# tps63020-buck-boost-flashlight-driver-te.net
KiCad netlist of a schematic drawn in EAGLE
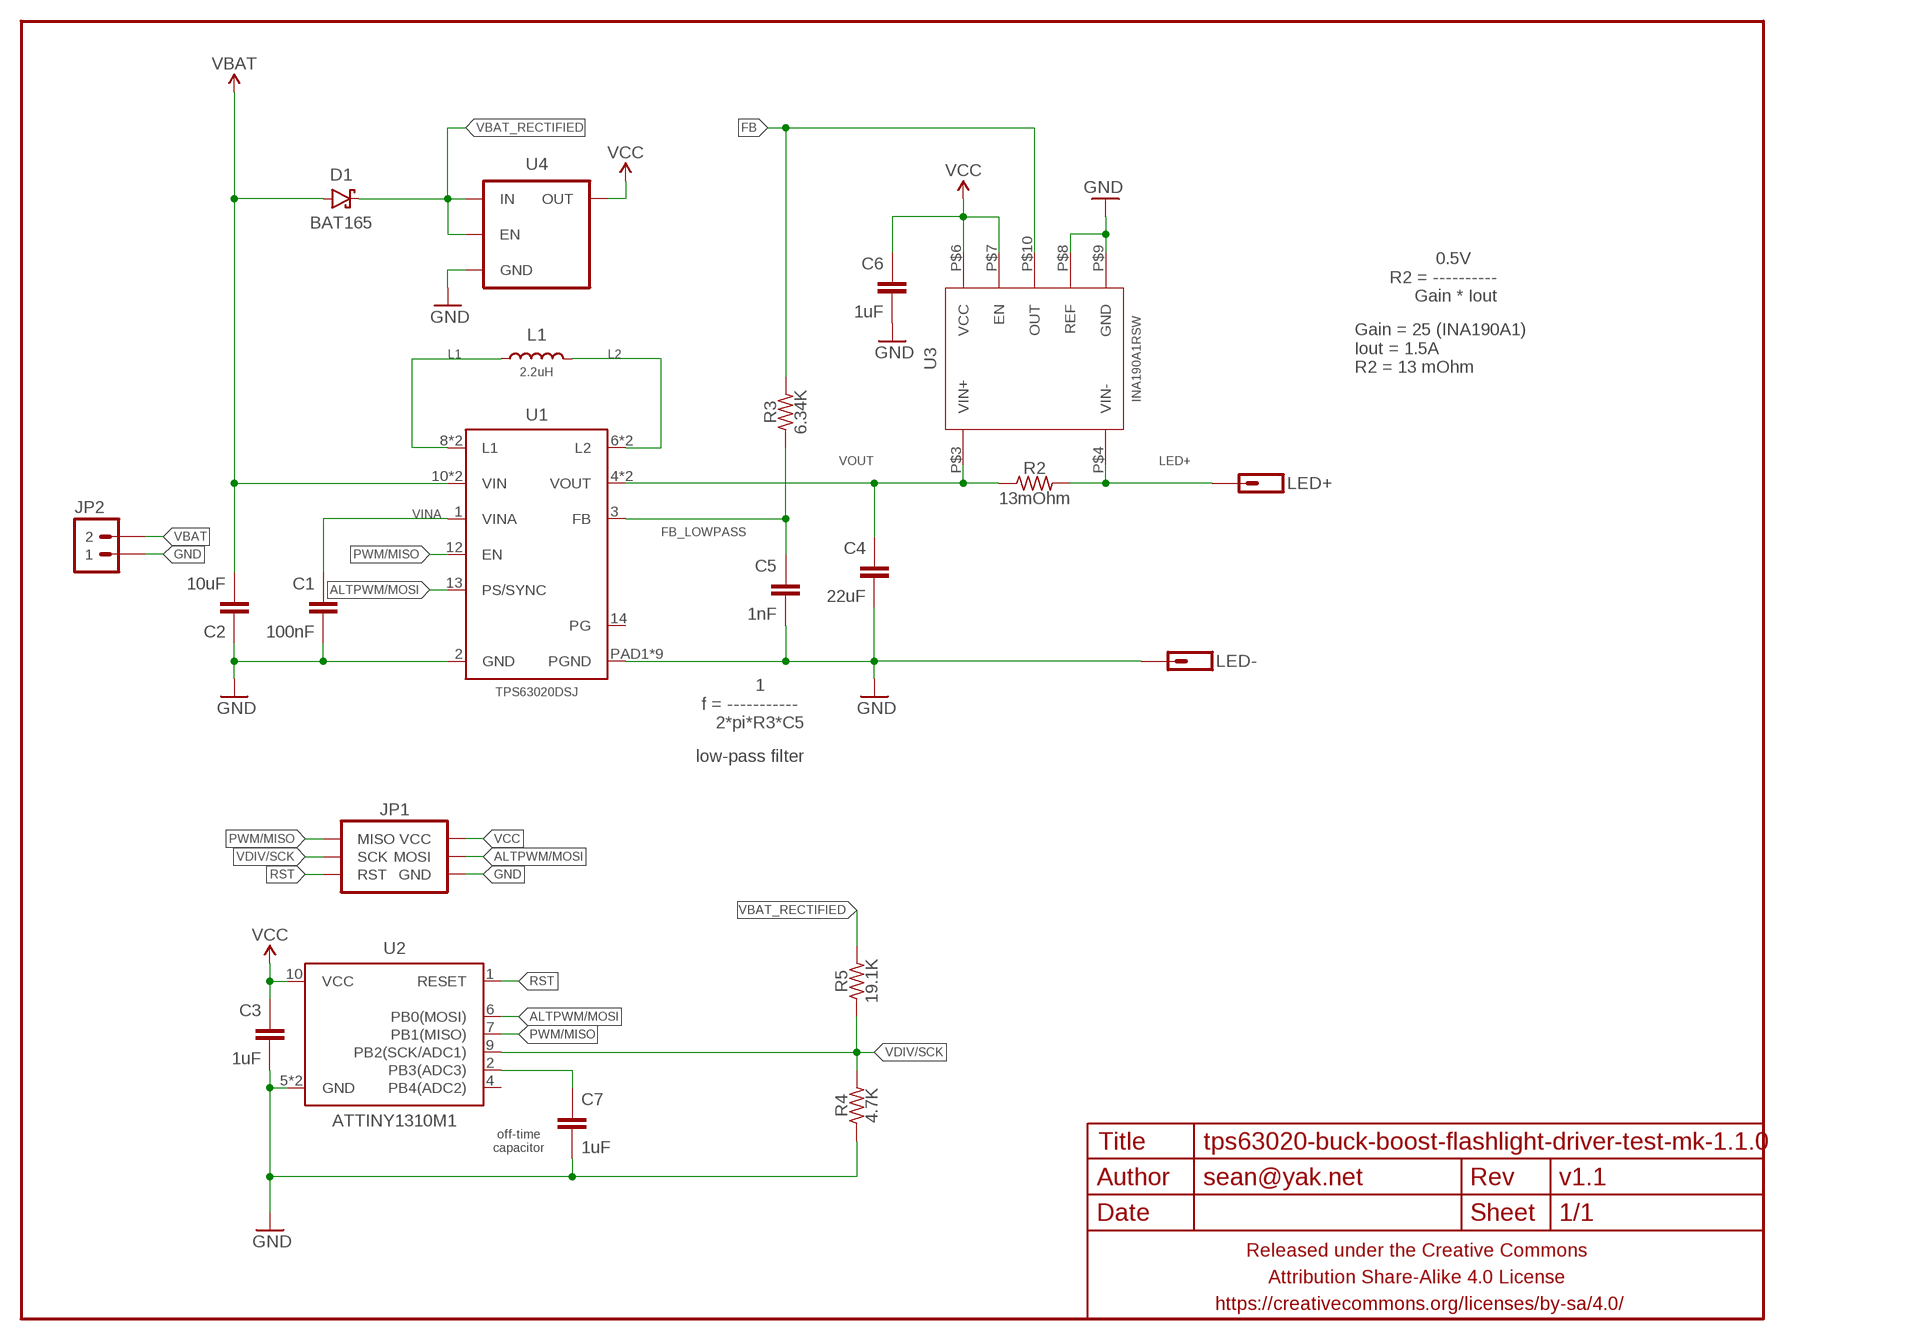
[diagram p0: schematic, sheet 1]

(export (version "E")
  (design (tool "Eeschema 10.0.6"))
  (components
    (comp (ref "C1")
      (value "100nF")
      (footprint "eagle-import:C0402")
      (libsource (lib "eagle-import") (part "CAPACITOR-CERAMICC0402"))
    )
    (comp (ref "C2")
      (value "10uF")
      (footprint "eagle-import:C0805-TIGHTER")
      (libsource (lib "eagle-import") (part "CAPACITOR-CERAMICC0805-TIGHTER"))
    )
    (comp (ref "C3")
      (value "1uF")
      (footprint "eagle-import:C0402")
      (libsource (lib "eagle-import") (part "CAPACITOR-CERAMICC0402"))
    )
    (comp (ref "C4")
      (value "22uF")
      (footprint "eagle-import:C1206")
      (libsource (lib "eagle-import") (part "CAPACITOR-CERAMICC1206"))
    )
    (comp (ref "C5")
      (value "1nF")
      (footprint "eagle-import:C0402")
      (libsource (lib "eagle-import") (part "CAPACITOR-CERAMICC0402"))
    )
    (comp (ref "C6")
      (value "1uF")
      (footprint "eagle-import:C0402")
      (libsource (lib "eagle-import") (part "CAPACITOR-CERAMICC0402"))
    )
    (comp (ref "C7")
      (value "1uF")
      (footprint "eagle-import:C0402")
      (libsource (lib "eagle-import") (part "CAPACITOR-CERAMICC0402"))
    )
    (comp (ref "D1")
      (value "BAT165")
      (footprint "eagle-import:SOD323-SCHOTTKY")
      (libsource (lib "eagle-import") (part "DIODE-SCHOTTKYSOD323"))
    )
    (comp (ref "FRAME1")
      (value "FRAME-LETTERNO_PACKAGE")
      (footprint "eagle-import:DUMMY")
      (fields
        (field (name "DESIGNER") "Nobody")
        (field (name "VERSION") "v01")
        (field (name "DESIGNER_1") "sean@yak.net")
        (field (name "VERSION_1") "v1.1")
      )
      (libsource (lib "eagle-import") (part "FRAME-LETTERNO_PACKAGE"))
    )
    (comp (ref "JP1")
      (value "AVR_SPI_PRG_6PTH-1.27MM")
      (footprint "eagle-import:2X3-1.27MM-PTH")
      (libsource (lib "eagle-import") (part "AVR_SPI_PRG_6PTH-1.27MM"))
    )
    (comp (ref "JP2")
      (value "M02PTH-2MM")
      (footprint "eagle-import:1X02-2MM-PTH")
      (libsource (lib "eagle-import") (part "M02PTH-2MM"))
    )
    (comp (ref "L1")
      (value "2.2uH")
      (footprint "eagle-import:XAL50X0")
      (libsource (lib "eagle-import") (part "INDUCTORXAL50X0"))
    )
    (comp (ref "LED+")
      (value "M01PTH-1MM-CIR-NS")
      (footprint "eagle-import:1X01-1MM-CIR-NS")
      (libsource (lib "eagle-import") (part "M01PTH-1MM-CIR-NS"))
    )
    (comp (ref "LED-")
      (value "M01PTH-1MM-CIR-NS")
      (footprint "eagle-import:1X01-1MM-CIR-NS")
      (libsource (lib "eagle-import") (part "M01PTH-1MM-CIR-NS"))
    )
    (comp (ref "R2")
      (value "13mOhm")
      (footprint "eagle-import:R1206")
      (libsource (lib "eagle-import") (part "RESISTORR1206"))
    )
    (comp (ref "R3")
      (value "6.34K")
      (footprint "eagle-import:R0402")
      (libsource (lib "eagle-import") (part "RESISTORR0402"))
    )
    (comp (ref "R4")
      (value "4.7K")
      (footprint "eagle-import:R0402")
      (libsource (lib "eagle-import") (part "RESISTORR0402"))
    )
    (comp (ref "R5")
      (value "19.1K")
      (footprint "eagle-import:R0402")
      (libsource (lib "eagle-import") (part "RESISTORR0402"))
    )
    (comp (ref "U1")
      (value "TPS63020DSJ")
      (footprint "eagle-import:VSON-14-4MMX3MM")
      (libsource (lib "eagle-import") (part "TPS63020DSJ"))
    )
    (comp (ref "U2")
      (value "ATTINY1310M1")
      (footprint "eagle-import:QFN10(2X5)")
      (libsource (lib "eagle-import") (part "ATTINY1310M1"))
    )
    (comp (ref "U3")
      (value "INA190A1RSW")
      (footprint "eagle-import:UQFN-10")
      (libsource (lib "eagle-import") (part "INA190RSW"))
    )
    (comp (ref "U4")
      (value "V_REG_ENTLV700")
      (footprint "eagle-import:SC70")
      (libsource (lib "eagle-import") (part "V_REG_ENTLV700"))
    )
  )
  (nets
    (net (code "1") (name "/FB_LOWPASS") (class "Default")
      (node (ref "C5") (pin "1") (pinfunction "1_1") (pintype "passive"))
      (node (ref "R3") (pin "1") (pinfunction "1_1") (pintype "passive"))
      (node (ref "U1") (pin "3") (pinfunction "FB_3") (pintype "bidirectional"))
    )
    (net (code "2") (name "/L1") (class "Default")
      (node (ref "L1") (pin "P$1") (pinfunction "1_P$1") (pintype "passive"))
      (node (ref "U1") (pin "8") (pinfunction "L1_8") (pintype "bidirectional"))
      (node (ref "U1") (pin "9") (pinfunction "L1_9") (pintype "bidirectional"))
    )
    (net (code "3") (name "/L2") (class "Default")
      (node (ref "L1") (pin "P$2") (pinfunction "2_P$2") (pintype "passive"))
      (node (ref "U1") (pin "6") (pinfunction "L2_6") (pintype "bidirectional"))
      (node (ref "U1") (pin "7") (pinfunction "L2_7") (pintype "bidirectional"))
    )
    (net (code "4") (name "/LED+") (class "Default")
      (node (ref "LED+") (pin "1") (pinfunction "1_1") (pintype "passive"))
      (node (ref "R2") (pin "2") (pinfunction "2_2") (pintype "passive"))
      (node (ref "U3") (pin "P$4") (pinfunction "VIN-_P$4") (pintype "bidirectional"))
    )
    (net (code "5") (name "/VINA") (class "Default")
      (node (ref "C1") (pin "1") (pinfunction "1_1") (pintype "passive"))
      (node (ref "U1") (pin "1") (pinfunction "VINA_1") (pintype "bidirectional"))
    )
    (net (code "6") (name "/VOUT") (class "Default")
      (node (ref "C4") (pin "1") (pinfunction "1_1") (pintype "passive"))
      (node (ref "R2") (pin "1") (pinfunction "1_1") (pintype "passive"))
      (node (ref "U1") (pin "4") (pinfunction "VOUT_4") (pintype "bidirectional"))
      (node (ref "U1") (pin "5") (pinfunction "VOUT_5") (pintype "bidirectional"))
      (node (ref "U3") (pin "P$3") (pinfunction "VIN+_P$3") (pintype "bidirectional"))
    )
    (net (code "7") (name "ALTPWM{slash}MOSI") (class "Default")
      (node (ref "JP1") (pin "4") (pinfunction "MOSI_4") (pintype "passive"))
      (node (ref "U1") (pin "13") (pinfunction "PS/SYNC_13") (pintype "bidirectional"))
      (node (ref "U2") (pin "6") (pinfunction "PB0(MOSI)_6") (pintype "bidirectional"))
    )
    (net (code "8") (name "FB") (class "Default")
      (node (ref "R3") (pin "2") (pinfunction "2_2") (pintype "passive"))
      (node (ref "U3") (pin "P$10") (pinfunction "OUT_P$10") (pintype "bidirectional"))
    )
    (net (code "9") (name "GND") (class "Default")
      (node (ref "C1") (pin "2") (pinfunction "2_2") (pintype "passive"))
      (node (ref "C2") (pin "1") (pinfunction "1_1") (pintype "passive"))
      (node (ref "C3") (pin "2") (pinfunction "2_2") (pintype "passive"))
      (node (ref "C4") (pin "2") (pinfunction "2_2") (pintype "passive"))
      (node (ref "C5") (pin "2") (pinfunction "2_2") (pintype "passive"))
      (node (ref "C6") (pin "2") (pinfunction "2_2") (pintype "passive"))
      (node (ref "C7") (pin "2") (pinfunction "2_2") (pintype "passive"))
      (node (ref "JP1") (pin "6") (pinfunction "GND_6") (pintype "passive"))
      (node (ref "JP2") (pin "P$1") (pinfunction "1_P$1") (pintype "passive"))
      (node (ref "LED-") (pin "1") (pinfunction "1_1") (pintype "passive"))
      (node (ref "R4") (pin "1") (pinfunction "1_1") (pintype "passive"))
      (node (ref "U1") (pin "2") (pinfunction "GND_2") (pintype "bidirectional"))
      (node (ref "U1") (pin "PAD1") (pinfunction "PGND_PAD1") (pintype "bidirectional"))
      (node (ref "U1") (pin "PAD2") (pinfunction "PGND_PAD2") (pintype "bidirectional"))
      (node (ref "U1") (pin "PAD3") (pinfunction "PGND_PAD3") (pintype "bidirectional"))
      (node (ref "U1") (pin "PAD4") (pinfunction "PGND_PAD4") (pintype "bidirectional"))
      (node (ref "U1") (pin "PAD5") (pinfunction "PGND_PAD5") (pintype "bidirectional"))
      (node (ref "U1") (pin "PAD6") (pinfunction "PGND_PAD6") (pintype "bidirectional"))
      (node (ref "U1") (pin "PAD7") (pinfunction "PGND_PAD7") (pintype "bidirectional"))
      (node (ref "U1") (pin "PAD8") (pinfunction "PGND_PAD8") (pintype "bidirectional"))
      (node (ref "U1") (pin "PADCENTER") (pinfunction "PGND_PADCENTER") (pintype "bidirectional"))
      (node (ref "U2") (pin "5") (pinfunction "GND_5") (pintype "bidirectional"))
      (node (ref "U2") (pin "PAD") (pinfunction "GND_PAD") (pintype "bidirectional"))
      (node (ref "U3") (pin "P$8") (pinfunction "REF_P$8") (pintype "bidirectional"))
      (node (ref "U3") (pin "P$9") (pinfunction "GND_P$9") (pintype "bidirectional"))
      (node (ref "U4") (pin "2") (pinfunction "GND_2") (pintype "input"))
    )
    (net (code "10") (name "Net-(U2-PB3(ADC3))") (class "Default")
      (node (ref "C7") (pin "1") (pinfunction "1_1") (pintype "passive"))
      (node (ref "U2") (pin "2") (pinfunction "PB3(ADC3)_2") (pintype "bidirectional"))
    )
    (net (code "11") (name "PWM{slash}MISO") (class "Default")
      (node (ref "JP1") (pin "1") (pinfunction "MISO_1") (pintype "passive"))
      (node (ref "U1") (pin "12") (pinfunction "EN_12") (pintype "bidirectional"))
      (node (ref "U2") (pin "7") (pinfunction "PB1(MISO)_7") (pintype "bidirectional"))
    )
    (net (code "12") (name "RST") (class "Default")
      (node (ref "JP1") (pin "5") (pinfunction "RST_5") (pintype "passive"))
      (node (ref "U2") (pin "1") (pinfunction "RESET_1") (pintype "bidirectional"))
    )
    (net (code "13") (name "VBAT") (class "Default")
      (node (ref "C2") (pin "2") (pinfunction "2_2") (pintype "passive"))
      (node (ref "D1") (pin "A") (pinfunction "A_A") (pintype "passive"))
      (node (ref "JP2") (pin "P$2") (pinfunction "2_P$2") (pintype "passive"))
      (node (ref "U1") (pin "10") (pinfunction "VIN_10") (pintype "bidirectional"))
      (node (ref "U1") (pin "11") (pinfunction "VIN_11") (pintype "bidirectional"))
    )
    (net (code "14") (name "VBAT_RECTIFIED") (class "Default")
      (node (ref "D1") (pin "C") (pinfunction "C_C") (pintype "passive"))
      (node (ref "R5") (pin "2") (pinfunction "2_2") (pintype "passive"))
      (node (ref "U4") (pin "1") (pinfunction "IN_1") (pintype "input"))
      (node (ref "U4") (pin "3") (pinfunction "EN_3") (pintype "input"))
    )
    (net (code "15") (name "VCC") (class "Default")
      (node (ref "C3") (pin "1") (pinfunction "1_1") (pintype "passive"))
      (node (ref "C6") (pin "1") (pinfunction "1_1") (pintype "passive"))
      (node (ref "JP1") (pin "2") (pinfunction "VCC_2") (pintype "passive"))
      (node (ref "U2") (pin "10") (pinfunction "VCC_10") (pintype "bidirectional"))
      (node (ref "U3") (pin "P$6") (pinfunction "VCC_P$6") (pintype "bidirectional"))
      (node (ref "U3") (pin "P$7") (pinfunction "EN_P$7") (pintype "bidirectional"))
      (node (ref "U4") (pin "5") (pinfunction "OUT_5") (pintype "passive"))
    )
    (net (code "16") (name "VDIV{slash}SCK") (class "Default")
      (node (ref "JP1") (pin "3") (pinfunction "SCK_3") (pintype "passive"))
      (node (ref "R4") (pin "2") (pinfunction "2_2") (pintype "passive"))
      (node (ref "R5") (pin "1") (pinfunction "1_1") (pintype "passive"))
      (node (ref "U2") (pin "9") (pinfunction "PB2(SCK/ADC1)_9") (pintype "bidirectional"))
    )
    (net (code "17") (name "unconnected-(U1-PG-Pad14)") (class "Default")
      (node (ref "U1") (pin "14") (pinfunction "PG_14") (pintype "bidirectional"))
    )
    (net (code "18") (name "unconnected-(U2-PB4(ADC2)-Pad4)") (class "Default")
      (node (ref "U2") (pin "4") (pinfunction "PB4(ADC2)_4") (pintype "bidirectional"))
    )
  )
)
